# 15-M2_GNSS.net
KiCad netlist of a schematic drawn in Altium Designer
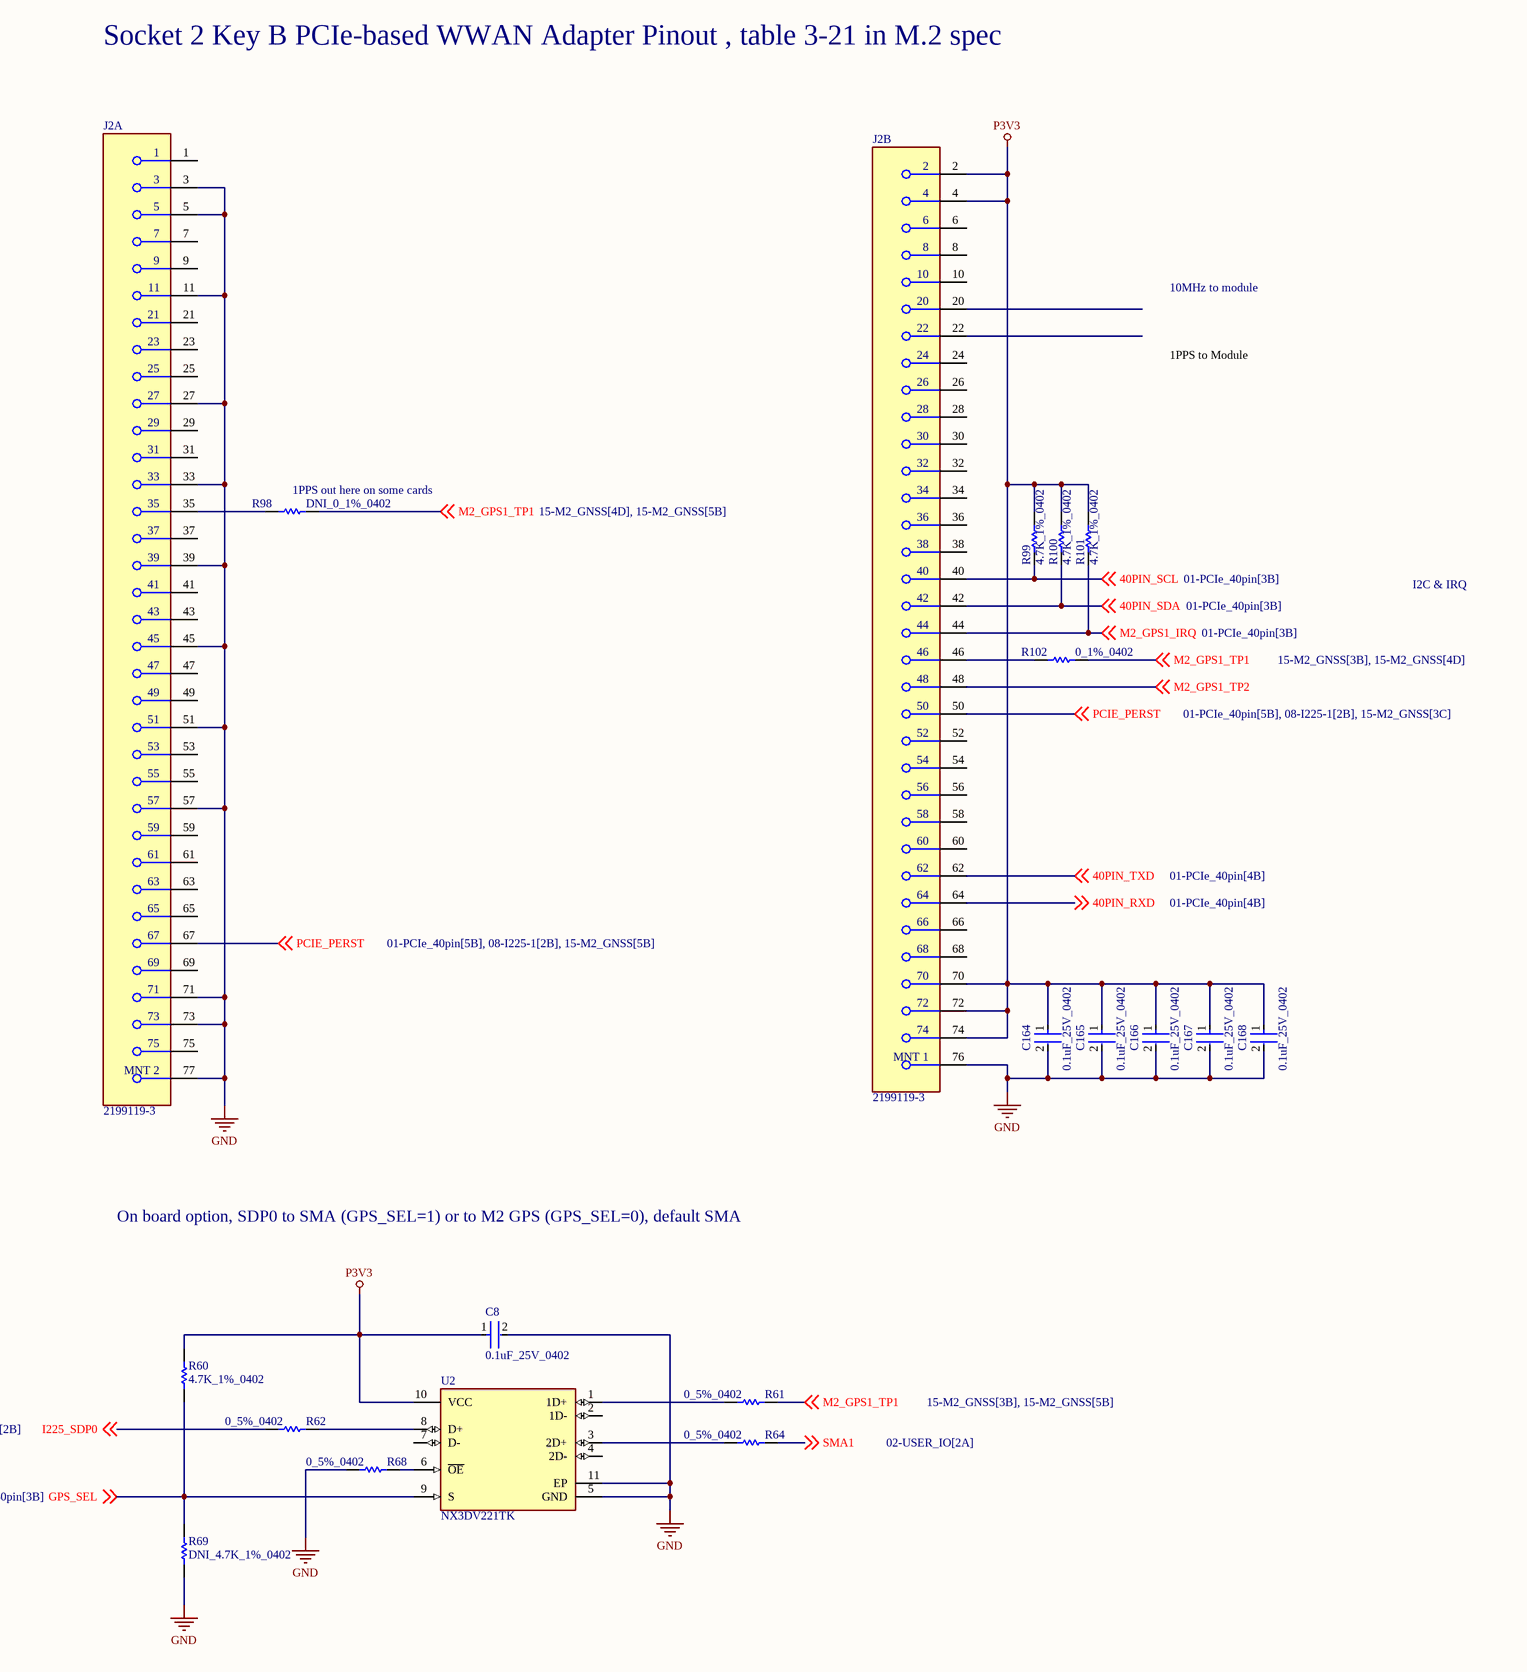
[diagram p0: 15-M2_GNSS.SchDoc]

(export (version "E")
  (design (tool "Eeschema 10.0.6"))
  (components
    (comp (ref "C8")
      (value "0.1uF_25V_0402")
      (footprint "FP-0402-L_1_0_1-W_0_5_0_1-IPC_C")
      (description "General Purpose Ceramic Capacitor, 0402, 100nF, 10%, X7R, 15%, 25V")
      (fields (field (name "VOLTAGE") "25V") (field (name "TOLERANCE") "10%"))
      (libsource (lib "Altium Content Vault") (part "b4654b650e69147ec39a6b967a45e02"))
    )
    (comp (ref "C164")
      (value "0.1uF_25V_0402")
      (footprint "FP-0402-L_1_0_1-W_0_5_0_1-IPC_C")
      (description "General Purpose Ceramic Capacitor, 0402, 100nF, 10%, X7R, 15%, 25V")
      (fields (field (name "VOLTAGE") "25V") (field (name "TOLERANCE") "10%"))
      (libsource (lib "Altium Content Vault") (part "b4654b650e69147ec39a6b967a45e02"))
    )
    (comp (ref "C165")
      (value "0.1uF_25V_0402")
      (footprint "FP-0402-L_1_0_1-W_0_5_0_1-IPC_C")
      (description "General Purpose Ceramic Capacitor, 0402, 100nF, 10%, X7R, 15%, 25V")
      (fields (field (name "VOLTAGE") "25V") (field (name "TOLERANCE") "10%"))
      (libsource (lib "Altium Content Vault") (part "b4654b650e69147ec39a6b967a45e02"))
    )
    (comp (ref "C166")
      (value "0.1uF_25V_0402")
      (footprint "FP-0402-L_1_0_1-W_0_5_0_1-IPC_C")
      (description "General Purpose Ceramic Capacitor, 0402, 100nF, 10%, X7R, 15%, 25V")
      (fields (field (name "VOLTAGE") "25V") (field (name "TOLERANCE") "10%"))
      (libsource (lib "Altium Content Vault") (part "b4654b650e69147ec39a6b967a45e02"))
    )
    (comp (ref "C167")
      (value "0.1uF_25V_0402")
      (footprint "FP-0402-L_1_0_1-W_0_5_0_1-IPC_C")
      (description "General Purpose Ceramic Capacitor, 0402, 100nF, 10%, X7R, 15%, 25V")
      (fields (field (name "VOLTAGE") "25V") (field (name "TOLERANCE") "10%"))
      (libsource (lib "Altium Content Vault") (part "b4654b650e69147ec39a6b967a45e02"))
    )
    (comp (ref "C168")
      (value "0.1uF_25V_0402")
      (footprint "FP-0402-L_1_0_1-W_0_5_0_1-IPC_C")
      (description "General Purpose Ceramic Capacitor, 0402, 100nF, 10%, X7R, 15%, 25V")
      (fields (field (name "VOLTAGE") "25V") (field (name "TOLERANCE") "10%"))
      (libsource (lib "Altium Content Vault") (part "b4654b650e69147ec39a6b967a45e02"))
    )
    (comp (ref "J2")
      (value "2199119-3")
      (footprint "FP-2199119-3-MFG")
      (description "CONN M.2 FEMALE 67POS 0.020 GOLD")
      (libsource (lib "Altium Content Vault") (part "a14843ccfa78e5d0b739856168502fb"))
    )
    (comp (ref "R60")
      (value "4.7K_1%_0402")
      (footprint "RESC1005X40X25NL10T10")
      (fields (field (name "MANUFACTURER") "Bourns") (field (name "PART NUMBER") "CR0402-FX-4701GLF"))
      (libsource (lib "Altium Content Vault") (part "RES"))
    )
    (comp (ref "R61")
      (value "0_5%_0402")
      (footprint "RESC1005X40X25LL10T10")
      (fields (field (name "MANUFACTURER") "KOA Speer") (field (name "PART NUMBER") "RK73Z1ETTP"))
      (libsource (lib "Altium Content Vault") (part "RES"))
    )
    (comp (ref "R62")
      (value "0_5%_0402")
      (footprint "RESC1005X40X25LL10T10")
      (fields (field (name "MANUFACTURER") "KOA Speer") (field (name "PART NUMBER") "RK73Z1ETTP"))
      (libsource (lib "Altium Content Vault") (part "RES"))
    )
    (comp (ref "R64")
      (value "0_5%_0402")
      (footprint "RESC1005X40X25LL10T10")
      (fields (field (name "MANUFACTURER") "KOA Speer") (field (name "PART NUMBER") "RK73Z1ETTP"))
      (libsource (lib "Altium Content Vault") (part "RES"))
    )
    (comp (ref "R68")
      (value "0_5%_0402")
      (footprint "RESC1005X40X25LL10T10")
      (fields (field (name "MANUFACTURER") "KOA Speer") (field (name "PART NUMBER") "RK73Z1ETTP"))
      (libsource (lib "Altium Content Vault") (part "RES"))
    )
    (comp (ref "R69")
      (value "DNI_4.7K_1%_0402")
      (footprint "RESC1005X40X25NL10T10")
      (fields (field (name "MANUFACTURER") "Bourns") (field (name "PART NUMBER") "CR0402-FX-4701GLF"))
      (libsource (lib "Altium Content Vault") (part "RES"))
    )
    (comp (ref "R98")
      (value "DNI_0_1%_0402")
      (footprint "RESC1005X40X25LL05T05")
      (description "Chip Resistor, 0 Ohm, 0.1 W, -55 to 155 degC, 0402 (1005 Metric), RoHS, Tape and Reel")
      (fields (field (name "MANUFACTURER") "Panasonic") (field (name "TOLERANCE") "5%"))
      (libsource (lib "Altium Content Vault") (part "RES-2"))
    )
    (comp (ref "R99")
      (value "4.7K_1%_0402")
      (footprint "RESC1005X40X25NL10T10")
      (fields (field (name "MANUFACTURER") "Bourns") (field (name "PART NUMBER") "CR0402-FX-4701GLF"))
      (libsource (lib "Altium Content Vault") (part "RES"))
    )
    (comp (ref "R100")
      (value "4.7K_1%_0402")
      (footprint "RESC1005X40X25NL10T10")
      (fields (field (name "MANUFACTURER") "Bourns") (field (name "PART NUMBER") "CR0402-FX-4701GLF"))
      (libsource (lib "Altium Content Vault") (part "RES"))
    )
    (comp (ref "R101")
      (value "4.7K_1%_0402")
      (footprint "RESC1005X40X25NL10T10")
      (fields (field (name "MANUFACTURER") "Bourns") (field (name "PART NUMBER") "CR0402-FX-4701GLF"))
      (libsource (lib "Altium Content Vault") (part "RES"))
    )
    (comp (ref "R102")
      (value "0_1%_0402")
      (footprint "RESC1005X40X25LL05T05")
      (description "Chip Resistor, 0 Ohm, 0.1 W, -55 to 155 degC, 0402 (1005 Metric), RoHS, Tape and Reel")
      (fields (field (name "MANUFACTURER") "Panasonic") (field (name "TOLERANCE") "5%"))
      (libsource (lib "Altium Content Vault") (part "RES-2"))
    )
    (comp (ref "U2")
      (value "NX3DV221TK")
      (footprint "FP-SOT650-2-MFG")
      (description "USB Switch IC 1 Channel 10-HVSON (3x3)")
      (libsource (lib "Altium Content Vault") (part "bce77ec48a709d17f0bdc2c26d779bf"))
    )
  )
  (nets
    (net (code "1") (name "40PIN_RXD") (class "Default")
      (node (ref "J2") (pin "64") (pinfunction "64_64") (pintype "passive"))
    )
    (net (code "2") (name "40PIN_SCL") (class "Default")
      (node (ref "J2") (pin "40") (pinfunction "40_40") (pintype "passive"))
      (node (ref "R99") (pin "1") (pinfunction "1_1") (pintype "passive"))
    )
    (net (code "3") (name "40PIN_SDA") (class "Default")
      (node (ref "J2") (pin "42") (pinfunction "42_42") (pintype "passive"))
      (node (ref "R100") (pin "1") (pinfunction "1_1") (pintype "passive"))
    )
    (net (code "4") (name "40PIN_TXD") (class "Default")
      (node (ref "J2") (pin "62") (pinfunction "62_62") (pintype "passive"))
    )
    (net (code "5") (name "GND") (class "Default")
      (node (ref "C164") (pin "2") (pinfunction "2_2") (pintype "passive"))
      (node (ref "C165") (pin "2") (pinfunction "2_2") (pintype "passive"))
      (node (ref "C166") (pin "2") (pinfunction "2_2") (pintype "passive"))
      (node (ref "C167") (pin "2") (pinfunction "2_2") (pintype "passive"))
      (node (ref "C168") (pin "2") (pinfunction "2_2") (pintype "passive"))
      (node (ref "C8") (pin "2") (pinfunction "2_2") (pintype "passive"))
      (node (ref "J2") (pin "11") (pinfunction "11_11") (pintype "passive"))
      (node (ref "J2") (pin "27") (pinfunction "27_27") (pintype "passive"))
      (node (ref "J2") (pin "3") (pinfunction "3_3") (pintype "passive"))
      (node (ref "J2") (pin "33") (pinfunction "33_33") (pintype "passive"))
      (node (ref "J2") (pin "39") (pinfunction "39_39") (pintype "passive"))
      (node (ref "J2") (pin "45") (pinfunction "45_45") (pintype "passive"))
      (node (ref "J2") (pin "5") (pinfunction "5_5") (pintype "passive"))
      (node (ref "J2") (pin "51") (pinfunction "51_51") (pintype "passive"))
      (node (ref "J2") (pin "57") (pinfunction "57_57") (pintype "passive"))
      (node (ref "J2") (pin "71") (pinfunction "71_71") (pintype "passive"))
      (node (ref "J2") (pin "73") (pinfunction "73_73") (pintype "passive"))
      (node (ref "J2") (pin "76") (pinfunction "MNT_1_76") (pintype "passive"))
      (node (ref "J2") (pin "77") (pinfunction "MNT_2_77") (pintype "passive"))
      (node (ref "R68") (pin "1") (pinfunction "1_1") (pintype "passive"))
      (node (ref "R69") (pin "2") (pinfunction "2_2") (pintype "passive"))
      (node (ref "U2") (pin "11") (pinfunction "EP_11") (pintype "passive"))
      (node (ref "U2") (pin "5") (pinfunction "GND_5") (pintype "power_in"))
    )
    (net (code "6") (name "GPS_SEL") (class "Default")
      (node (ref "R60") (pin "2") (pinfunction "2_2") (pintype "passive"))
      (node (ref "R69") (pin "1") (pinfunction "1_1") (pintype "passive"))
      (node (ref "U2") (pin "9") (pinfunction "S_9") (pintype "input"))
    )
    (net (code "7") (name "I225_SDP0") (class "Default")
      (node (ref "R62") (pin "1") (pinfunction "1_1") (pintype "passive"))
    )
    (net (code "8") (name "M2_GPS1_IRQ") (class "Default")
      (node (ref "J2") (pin "44") (pinfunction "44_44") (pintype "passive"))
      (node (ref "R101") (pin "1") (pinfunction "1_1") (pintype "passive"))
    )
    (net (code "9") (name "M2_GPS1_TP1") (class "Default")
      (node (ref "R102") (pin "2") (pinfunction "2_2") (pintype "passive"))
      (node (ref "R61") (pin "2") (pinfunction "2_2") (pintype "passive"))
      (node (ref "R98") (pin "2") (pinfunction "2_2") (pintype "passive"))
    )
    (net (code "10") (name "M2_GPS1_TP2") (class "Default")
      (node (ref "J2") (pin "48") (pinfunction "48_48") (pintype "passive"))
    )
    (net (code "11") (name "Net-(J2-Pad35)") (class "Default")
      (node (ref "J2") (pin "35") (pinfunction "35_35") (pintype "passive"))
      (node (ref "R98") (pin "1") (pinfunction "1_1") (pintype "passive"))
    )
    (net (code "12") (name "Net-(J2-Pad46)") (class "Default")
      (node (ref "J2") (pin "46") (pinfunction "46_46") (pintype "passive"))
      (node (ref "R102") (pin "1") (pinfunction "1_1") (pintype "passive"))
    )
    (net (code "13") (name "Net-(U2-1D+)") (class "Default")
      (node (ref "R61") (pin "1") (pinfunction "1_1") (pintype "passive"))
      (node (ref "U2") (pin "1") (pinfunction "1D+_1") (pintype "bidirectional"))
    )
    (net (code "14") (name "Net-(U2-2D+)") (class "Default")
      (node (ref "R64") (pin "1") (pinfunction "1_1") (pintype "passive"))
      (node (ref "U2") (pin "3") (pinfunction "2D+_3") (pintype "bidirectional"))
    )
    (net (code "15") (name "Net-(U2-D+)") (class "Default")
      (node (ref "R62") (pin "2") (pinfunction "2_2") (pintype "passive"))
      (node (ref "U2") (pin "8") (pinfunction "D+_8") (pintype "bidirectional"))
    )
    (net (code "16") (name "Net-(U2-~{OE})") (class "Default")
      (node (ref "R68") (pin "2") (pinfunction "2_2") (pintype "passive"))
      (node (ref "U2") (pin "6") (pinfunction "~{OE}_6") (pintype "input"))
    )
    (net (code "17") (name "P3V3") (class "Default")
      (node (ref "C164") (pin "1") (pinfunction "1_1") (pintype "passive"))
      (node (ref "C165") (pin "1") (pinfunction "1_1") (pintype "passive"))
      (node (ref "C166") (pin "1") (pinfunction "1_1") (pintype "passive"))
      (node (ref "C167") (pin "1") (pinfunction "1_1") (pintype "passive"))
      (node (ref "C168") (pin "1") (pinfunction "1_1") (pintype "passive"))
      (node (ref "C8") (pin "1") (pinfunction "1_1") (pintype "passive"))
      (node (ref "J2") (pin "2") (pinfunction "2_2") (pintype "passive"))
      (node (ref "J2") (pin "4") (pinfunction "4_4") (pintype "passive"))
      (node (ref "J2") (pin "70") (pinfunction "70_70") (pintype "passive"))
      (node (ref "J2") (pin "72") (pinfunction "72_72") (pintype "passive"))
      (node (ref "J2") (pin "74") (pinfunction "74_74") (pintype "passive"))
      (node (ref "R100") (pin "2") (pinfunction "2_2") (pintype "passive"))
      (node (ref "R101") (pin "2") (pinfunction "2_2") (pintype "passive"))
      (node (ref "R60") (pin "1") (pinfunction "1_1") (pintype "passive"))
      (node (ref "R99") (pin "2") (pinfunction "2_2") (pintype "passive"))
      (node (ref "U2") (pin "10") (pinfunction "VCC_10") (pintype "power_in"))
    )
    (net (code "18") (name "PCIE_PERST") (class "Default")
      (node (ref "J2") (pin "50") (pinfunction "50_50") (pintype "passive"))
      (node (ref "J2") (pin "67") (pinfunction "67_67") (pintype "passive"))
    )
    (net (code "19") (name "SMA1") (class "Default")
      (node (ref "R64") (pin "2") (pinfunction "2_2") (pintype "passive"))
    )
    (net (code "20") (name "unconnected-(J2-Pad1)") (class "Default")
      (node (ref "J2") (pin "1") (pinfunction "1_1") (pintype "passive"))
    )
    (net (code "21") (name "unconnected-(J2-Pad6)") (class "Default")
      (node (ref "J2") (pin "6") (pinfunction "6_6") (pintype "passive"))
    )
    (net (code "22") (name "unconnected-(J2-Pad7)") (class "Default")
      (node (ref "J2") (pin "7") (pinfunction "7_7") (pintype "passive"))
    )
    (net (code "23") (name "unconnected-(J2-Pad8)") (class "Default")
      (node (ref "J2") (pin "8") (pinfunction "8_8") (pintype "passive"))
    )
    (net (code "24") (name "unconnected-(J2-Pad9)") (class "Default")
      (node (ref "J2") (pin "9") (pinfunction "9_9") (pintype "passive"))
    )
    (net (code "25") (name "unconnected-(J2-Pad10)") (class "Default")
      (node (ref "J2") (pin "10") (pinfunction "10_10") (pintype "passive"))
    )
    (net (code "26") (name "unconnected-(J2-Pad20)") (class "Default")
      (node (ref "J2") (pin "20") (pinfunction "20_20") (pintype "passive"))
    )
    (net (code "27") (name "unconnected-(J2-Pad21)") (class "Default")
      (node (ref "J2") (pin "21") (pinfunction "21_21") (pintype "passive"))
    )
    (net (code "28") (name "unconnected-(J2-Pad22)") (class "Default")
      (node (ref "J2") (pin "22") (pinfunction "22_22") (pintype "passive"))
    )
    (net (code "29") (name "unconnected-(J2-Pad23)") (class "Default")
      (node (ref "J2") (pin "23") (pinfunction "23_23") (pintype "passive"))
    )
    (net (code "30") (name "unconnected-(J2-Pad24)") (class "Default")
      (node (ref "J2") (pin "24") (pinfunction "24_24") (pintype "passive"))
    )
    (net (code "31") (name "unconnected-(J2-Pad25)") (class "Default")
      (node (ref "J2") (pin "25") (pinfunction "25_25") (pintype "passive"))
    )
    (net (code "32") (name "unconnected-(J2-Pad26)") (class "Default")
      (node (ref "J2") (pin "26") (pinfunction "26_26") (pintype "passive"))
    )
    (net (code "33") (name "unconnected-(J2-Pad28)") (class "Default")
      (node (ref "J2") (pin "28") (pinfunction "28_28") (pintype "passive"))
    )
    (net (code "34") (name "unconnected-(J2-Pad29)") (class "Default")
      (node (ref "J2") (pin "29") (pinfunction "29_29") (pintype "passive"))
    )
    (net (code "35") (name "unconnected-(J2-Pad30)") (class "Default")
      (node (ref "J2") (pin "30") (pinfunction "30_30") (pintype "passive"))
    )
    (net (code "36") (name "unconnected-(J2-Pad31)") (class "Default")
      (node (ref "J2") (pin "31") (pinfunction "31_31") (pintype "passive"))
    )
    (net (code "37") (name "unconnected-(J2-Pad32)") (class "Default")
      (node (ref "J2") (pin "32") (pinfunction "32_32") (pintype "passive"))
    )
    (net (code "38") (name "unconnected-(J2-Pad34)") (class "Default")
      (node (ref "J2") (pin "34") (pinfunction "34_34") (pintype "passive"))
    )
    (net (code "39") (name "unconnected-(J2-Pad36)") (class "Default")
      (node (ref "J2") (pin "36") (pinfunction "36_36") (pintype "passive"))
    )
    (net (code "40") (name "unconnected-(J2-Pad37)") (class "Default")
      (node (ref "J2") (pin "37") (pinfunction "37_37") (pintype "passive"))
    )
    (net (code "41") (name "unconnected-(J2-Pad38)") (class "Default")
      (node (ref "J2") (pin "38") (pinfunction "38_38") (pintype "passive"))
    )
    (net (code "42") (name "unconnected-(J2-Pad41)") (class "Default")
      (node (ref "J2") (pin "41") (pinfunction "41_41") (pintype "passive"))
    )
    (net (code "43") (name "unconnected-(J2-Pad43)") (class "Default")
      (node (ref "J2") (pin "43") (pinfunction "43_43") (pintype "passive"))
    )
    (net (code "44") (name "unconnected-(J2-Pad47)") (class "Default")
      (node (ref "J2") (pin "47") (pinfunction "47_47") (pintype "passive"))
    )
    (net (code "45") (name "unconnected-(J2-Pad49)") (class "Default")
      (node (ref "J2") (pin "49") (pinfunction "49_49") (pintype "passive"))
    )
    (net (code "46") (name "unconnected-(J2-Pad52)") (class "Default")
      (node (ref "J2") (pin "52") (pinfunction "52_52") (pintype "passive"))
    )
    (net (code "47") (name "unconnected-(J2-Pad53)") (class "Default")
      (node (ref "J2") (pin "53") (pinfunction "53_53") (pintype "passive"))
    )
    (net (code "48") (name "unconnected-(J2-Pad54)") (class "Default")
      (node (ref "J2") (pin "54") (pinfunction "54_54") (pintype "passive"))
    )
    (net (code "49") (name "unconnected-(J2-Pad55)") (class "Default")
      (node (ref "J2") (pin "55") (pinfunction "55_55") (pintype "passive"))
    )
    (net (code "50") (name "unconnected-(J2-Pad56)") (class "Default")
      (node (ref "J2") (pin "56") (pinfunction "56_56") (pintype "passive"))
    )
    (net (code "51") (name "unconnected-(J2-Pad58)") (class "Default")
      (node (ref "J2") (pin "58") (pinfunction "58_58") (pintype "passive"))
    )
    (net (code "52") (name "unconnected-(J2-Pad59)") (class "Default")
      (node (ref "J2") (pin "59") (pinfunction "59_59") (pintype "passive"))
    )
    (net (code "53") (name "unconnected-(J2-Pad60)") (class "Default")
      (node (ref "J2") (pin "60") (pinfunction "60_60") (pintype "passive"))
    )
    (net (code "54") (name "unconnected-(J2-Pad61)") (class "Default")
      (node (ref "J2") (pin "61") (pinfunction "61_61") (pintype "passive"))
    )
    (net (code "55") (name "unconnected-(J2-Pad63)") (class "Default")
      (node (ref "J2") (pin "63") (pinfunction "63_63") (pintype "passive"))
    )
    (net (code "56") (name "unconnected-(J2-Pad65)") (class "Default")
      (node (ref "J2") (pin "65") (pinfunction "65_65") (pintype "passive"))
    )
    (net (code "57") (name "unconnected-(J2-Pad66)") (class "Default")
      (node (ref "J2") (pin "66") (pinfunction "66_66") (pintype "passive"))
    )
    (net (code "58") (name "unconnected-(J2-Pad68)") (class "Default")
      (node (ref "J2") (pin "68") (pinfunction "68_68") (pintype "passive"))
    )
    (net (code "59") (name "unconnected-(J2-Pad69)") (class "Default")
      (node (ref "J2") (pin "69") (pinfunction "69_69") (pintype "passive"))
    )
    (net (code "60") (name "unconnected-(J2-Pad75)") (class "Default")
      (node (ref "J2") (pin "75") (pinfunction "75_75") (pintype "passive"))
    )
    (net (code "61") (name "unconnected-(U2-1D--Pad2)") (class "Default")
      (node (ref "U2") (pin "2") (pinfunction "1D-_2") (pintype "bidirectional"))
    )
    (net (code "62") (name "unconnected-(U2-2D--Pad4)") (class "Default")
      (node (ref "U2") (pin "4") (pinfunction "2D-_4") (pintype "bidirectional"))
    )
    (net (code "63") (name "unconnected-(U2-D--Pad7)") (class "Default")
      (node (ref "U2") (pin "7") (pinfunction "D-_7") (pintype "bidirectional"))
    )
  )
)
